# power_supply.net
KiCad netlist of a schematic drawn in Altium Designer
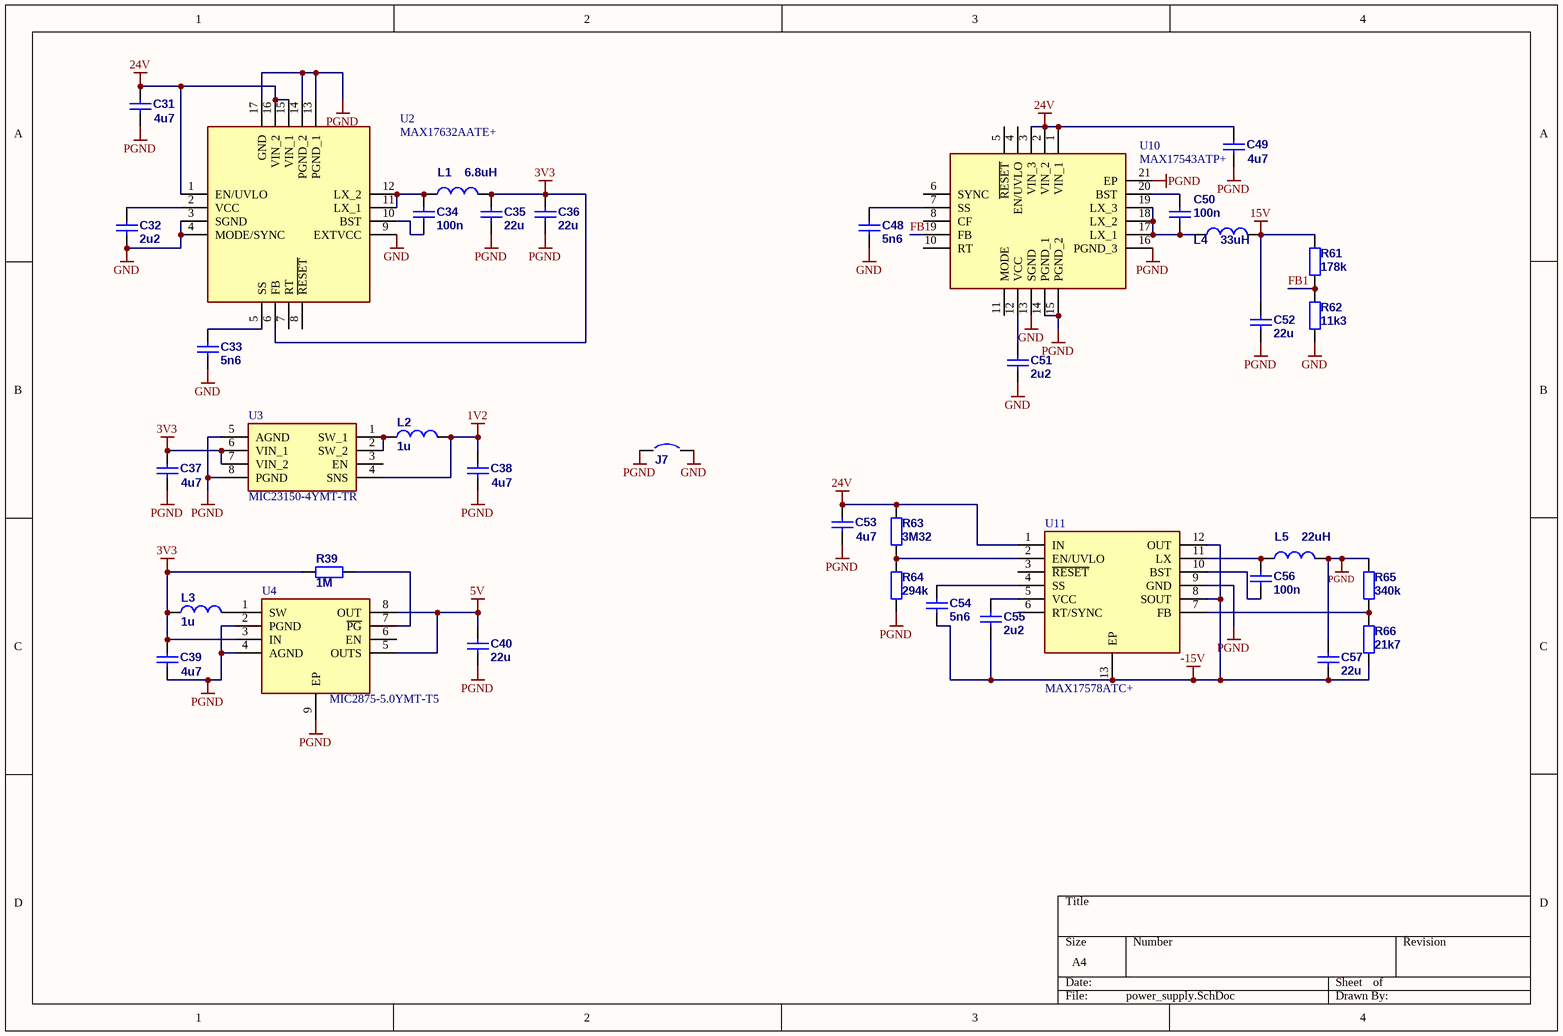
[diagram p0: power_supply.SchDoc]

(export (version "E")
  (design (tool "Eeschema 10.0.6"))
  (components
    (comp (ref "C31")
      (value "4u7")
      (footprint "C1206")
      (description "Capacitor")
      (libsource (lib "capacitors") (part "Cap"))
    )
    (comp (ref "C32")
      (value "2u2")
      (footprint "C0603")
      (description "Capacitor")
      (libsource (lib "capacitors") (part "Cap"))
    )
    (comp (ref "C33")
      (value "5n6")
      (footprint "C0603")
      (description "Capacitor")
      (libsource (lib "capacitors") (part "Cap"))
    )
    (comp (ref "C34")
      (value "100n")
      (footprint "C0603")
      (description "Capacitor")
      (libsource (lib "capacitors") (part "Cap"))
    )
    (comp (ref "C35")
      (value "22u")
      (footprint "C1206")
      (description "Capacitor")
      (libsource (lib "capacitors") (part "Cap"))
    )
    (comp (ref "C36")
      (value "22u")
      (footprint "C1206")
      (description "Capacitor")
      (libsource (lib "capacitors") (part "Cap"))
    )
    (comp (ref "C37")
      (value "4u7")
      (footprint "C1206")
      (description "Capacitor")
      (libsource (lib "capacitors") (part "Cap"))
    )
    (comp (ref "C38")
      (value "4u7")
      (footprint "C1206")
      (description "Capacitor")
      (libsource (lib "capacitors") (part "Cap"))
    )
    (comp (ref "C39")
      (value "4u7")
      (footprint "C1206")
      (description "Capacitor")
      (libsource (lib "capacitors") (part "Cap"))
    )
    (comp (ref "C40")
      (value "22u")
      (footprint "C1206")
      (description "Capacitor")
      (libsource (lib "capacitors") (part "Cap"))
    )
    (comp (ref "C48")
      (value "5n6")
      (footprint "C0603")
      (description "Capacitor")
      (libsource (lib "capacitors") (part "Cap"))
    )
    (comp (ref "C49")
      (value "4u7")
      (footprint "C1206")
      (description "Capacitor")
      (libsource (lib "capacitors") (part "Cap"))
    )
    (comp (ref "C50")
      (value "100n")
      (footprint "C0603")
      (description "Capacitor")
      (libsource (lib "capacitors") (part "Cap"))
    )
    (comp (ref "C51")
      (value "2u2")
      (footprint "C0603")
      (description "Capacitor")
      (libsource (lib "capacitors") (part "Cap"))
    )
    (comp (ref "C52")
      (value "22u")
      (footprint "C1206")
      (description "Capacitor")
      (libsource (lib "capacitors") (part "Cap"))
    )
    (comp (ref "C53")
      (value "4u7")
      (footprint "C1206")
      (description "Capacitor")
      (libsource (lib "capacitors") (part "Cap"))
    )
    (comp (ref "C54")
      (value "5n6")
      (footprint "C0603")
      (description "Capacitor")
      (libsource (lib "capacitors") (part "Cap"))
    )
    (comp (ref "C55")
      (value "2u2")
      (footprint "C0603")
      (description "Capacitor")
      (libsource (lib "capacitors") (part "Cap"))
    )
    (comp (ref "C56")
      (value "100n")
      (footprint "C0603")
      (description "Capacitor")
      (libsource (lib "capacitors") (part "Cap"))
    )
    (comp (ref "C57")
      (value "22u")
      (footprint "C1206")
      (description "Capacitor")
      (libsource (lib "capacitors") (part "Cap"))
    )
    (comp (ref "J7")
      (value "Circuit Breaker")
      (footprint "JMP2_0805_N_NC")
      (fields (field (name "PUBLISHER") "Altium Limited"))
      (libsource (lib "jumpers_and_circuit_brakers") (part "Circuit Breaker"))
    )
    (comp (ref "L1")
      (value "6.8uH")
      (footprint "DE1205")
      (description "DE1205-10")
      (libsource (lib "inductors") (part "DE1205-10"))
    )
    (comp (ref "L2")
      (value "1u")
      (footprint "L1210")
      (description "Inductor")
      (libsource (lib "inductors") (part "Ind"))
    )
    (comp (ref "L3")
      (value "1u")
      (footprint "L1210")
      (description "Inductor")
      (libsource (lib "inductors") (part "Ind"))
    )
    (comp (ref "L4")
      (value "33uH")
      (footprint "DE1205")
      (description "DE1205-22")
      (libsource (lib "inductors") (part "DE1205-22"))
    )
    (comp (ref "L5")
      (value "22uH")
      (footprint "DE1205")
      (description "DE1205-22")
      (libsource (lib "inductors") (part "DE1205-22"))
    )
    (comp (ref "R39")
      (value "1M")
      (footprint "R0603")
      (description "Resistor")
      (libsource (lib "") (part "Res_1"))
    )
    (comp (ref "R61")
      (value "178k")
      (footprint "R0603")
      (description "Resistor")
      (libsource (lib "resistors") (part "Res"))
    )
    (comp (ref "R62")
      (value "11k3")
      (footprint "R0603")
      (description "Resistor")
      (libsource (lib "resistors") (part "Res"))
    )
    (comp (ref "R63")
      (value "3M32")
      (footprint "R0603")
      (description "Resistor")
      (libsource (lib "resistors") (part "Res"))
    )
    (comp (ref "R64")
      (value "294k")
      (footprint "R0603")
      (description "Resistor")
      (libsource (lib "resistors") (part "Res"))
    )
    (comp (ref "R65")
      (value "340k")
      (footprint "R0603")
      (description "Resistor")
      (libsource (lib "resistors") (part "Res"))
    )
    (comp (ref "R66")
      (value "21k7")
      (footprint "R0603")
      (description "Resistor")
      (libsource (lib "resistors") (part "Res"))
    )
    (comp (ref "U2")
      (value "MAX17632AATE+")
      (footprint "SamacSys:QFN50P300X300X80-17N")
      (description "Integrated Circuit")
      (libsource (lib "*") (part "MAX17632AATE+"))
    )
    (comp (ref "U3")
      (value "MIC23150-4YMT-TR")
      (footprint "SamacSys:MIC231504YMTTR")
      (description "Integrated Circuit")
      (fields (field (name "MOUSER PART NUMBER") "998-MIC23150-4YMTTR"))
      (libsource (lib "*") (part "MIC23150-4YMT-TR"))
    )
    (comp (ref "U4")
      (value "MIC2875-5.0YMT-T5")
      (footprint "SamacSys:SON50P200X200X60-9N-D")
      (description "Integrated Circuit")
      (libsource (lib "*") (part "MIC2875-5.0YMT-T5"))
    )
    (comp (ref "U10")
      (value "MAX17543ATP+")
      (footprint "SamacSys:QFN50P400X400X80-21N")
      (description "Integrated Circuit")
      (libsource (lib "*") (part "MAX17543ATP+"))
    )
    (comp (ref "U11")
      (value "MAX17578ATC+")
      (footprint "SamacSys:SON50P300X300X80-13N")
      (description "Integrated Circuit")
      (libsource (lib "*") (part "MAX17578ATC+"))
    )
  )
  (nets
    (net (code "1") (name "-15V") (class "Default")
      (node (ref "C54") (pin "1") (pinfunction "1_1") (pintype "passive"))
      (node (ref "C55") (pin "1") (pinfunction "1_1") (pintype "passive"))
      (node (ref "C57") (pin "1") (pinfunction "1_1") (pintype "passive"))
      (node (ref "R66") (pin "1") (pinfunction "1_1") (pintype "passive"))
      (node (ref "U11") (pin "12") (pinfunction "OUT_12") (pintype "passive"))
      (node (ref "U11") (pin "13") (pinfunction "EP_13") (pintype "passive"))
      (node (ref "U11") (pin "8") (pinfunction "SOUT_8") (pintype "passive"))
    )
    (net (code "2") (name "/FB1") (class "Default")
      (node (ref "R61") (pin "1") (pinfunction "1_1") (pintype "passive"))
      (node (ref "R62") (pin "2") (pinfunction "2_2") (pintype "passive"))
      (node (ref "U10") (pin "9") (pinfunction "FB_9") (pintype "passive"))
    )
    (net (code "3") (name "1V2") (class "Default")
      (node (ref "C38") (pin "2") (pinfunction "2_2") (pintype "passive"))
      (node (ref "L2") (pin "2") (pinfunction "2_2") (pintype "passive"))
      (node (ref "U3") (pin "4") (pinfunction "SNS_4") (pintype "passive"))
    )
    (net (code "4") (name "3V3") (class "Default")
      (node (ref "C35") (pin "2") (pinfunction "2_2") (pintype "passive"))
      (node (ref "C36") (pin "2") (pinfunction "2_2") (pintype "passive"))
      (node (ref "C37") (pin "2") (pinfunction "2_2") (pintype "passive"))
      (node (ref "C39") (pin "2") (pinfunction "2_2") (pintype "passive"))
      (node (ref "L1") (pin "2") (pinfunction "2_2") (pintype "passive"))
      (node (ref "L3") (pin "1") (pinfunction "1_1") (pintype "passive"))
      (node (ref "R39") (pin "1") (pinfunction "1_1") (pintype "passive"))
      (node (ref "U2") (pin "6") (pinfunction "FB_6") (pintype "passive"))
      (node (ref "U3") (pin "6") (pinfunction "VIN_1_6") (pintype "passive"))
      (node (ref "U3") (pin "7") (pinfunction "VIN_2_7") (pintype "passive"))
      (node (ref "U4") (pin "3") (pinfunction "IN_3") (pintype "passive"))
    )
    (net (code "5") (name "5V") (class "Default")
      (node (ref "C40") (pin "2") (pinfunction "2_2") (pintype "passive"))
      (node (ref "U4") (pin "5") (pinfunction "OUTS_5") (pintype "passive"))
      (node (ref "U4") (pin "8") (pinfunction "OUT_8") (pintype "passive"))
    )
    (net (code "6") (name "15V") (class "Default")
      (node (ref "C52") (pin "2") (pinfunction "2_2") (pintype "passive"))
      (node (ref "L4") (pin "2") (pinfunction "2_2") (pintype "passive"))
      (node (ref "R61") (pin "2") (pinfunction "2_2") (pintype "passive"))
    )
    (net (code "7") (name "24V") (class "Default")
      (node (ref "C31") (pin "2") (pinfunction "2_2") (pintype "passive"))
      (node (ref "C49") (pin "2") (pinfunction "2_2") (pintype "passive"))
      (node (ref "C53") (pin "2") (pinfunction "2_2") (pintype "passive"))
      (node (ref "R63") (pin "2") (pinfunction "2_2") (pintype "passive"))
      (node (ref "U10") (pin "1") (pinfunction "VIN_1_1") (pintype "passive"))
      (node (ref "U10") (pin "2") (pinfunction "VIN_2_2") (pintype "passive"))
      (node (ref "U10") (pin "3") (pinfunction "VIN_3_3") (pintype "passive"))
      (node (ref "U11") (pin "1") (pinfunction "IN_1") (pintype "passive"))
      (node (ref "U2") (pin "1") (pinfunction "EN/UVLO_1") (pintype "passive"))
      (node (ref "U2") (pin "15") (pinfunction "VIN_1_15") (pintype "passive"))
      (node (ref "U2") (pin "16") (pinfunction "VIN_2_16") (pintype "passive"))
    )
    (net (code "8") (name "GND") (class "Default")
      (node (ref "C32") (pin "1") (pinfunction "1_1") (pintype "passive"))
      (node (ref "C33") (pin "1") (pinfunction "1_1") (pintype "passive"))
      (node (ref "C48") (pin "1") (pinfunction "1_1") (pintype "passive"))
      (node (ref "C51") (pin "1") (pinfunction "1_1") (pintype "passive"))
      (node (ref "J7") (pin "2") (pinfunction "2_2") (pintype "passive"))
      (node (ref "R62") (pin "1") (pinfunction "1_1") (pintype "passive"))
      (node (ref "U10") (pin "13") (pinfunction "SGND_13") (pintype "passive"))
      (node (ref "U2") (pin "3") (pinfunction "SGND_3") (pintype "passive"))
      (node (ref "U2") (pin "4") (pinfunction "MODE/SYNC_4") (pintype "passive"))
      (node (ref "U2") (pin "9") (pinfunction "EXTVCC_9") (pintype "passive"))
    )
    (net (code "9") (name "Net-(U2-BST)") (class "Default")
      (node (ref "C34") (pin "2") (pinfunction "2_2") (pintype "passive"))
      (node (ref "U2") (pin "10") (pinfunction "BST_10") (pintype "passive"))
    )
    (net (code "10") (name "Net-(U2-LX_1)") (class "Default")
      (node (ref "C34") (pin "1") (pinfunction "1_1") (pintype "passive"))
      (node (ref "L1") (pin "1") (pinfunction "1_1") (pintype "passive"))
      (node (ref "U2") (pin "11") (pinfunction "LX_1_11") (pintype "passive"))
      (node (ref "U2") (pin "12") (pinfunction "LX_2_12") (pintype "passive"))
    )
    (net (code "11") (name "Net-(U2-SS)") (class "Default")
      (node (ref "C33") (pin "2") (pinfunction "2_2") (pintype "passive"))
      (node (ref "U2") (pin "5") (pinfunction "SS_5") (pintype "passive"))
    )
    (net (code "12") (name "Net-(U2-VCC)") (class "Default")
      (node (ref "C32") (pin "2") (pinfunction "2_2") (pintype "passive"))
      (node (ref "U2") (pin "2") (pinfunction "VCC_2") (pintype "passive"))
    )
    (net (code "13") (name "Net-(U3-SW_1)") (class "Default")
      (node (ref "L2") (pin "1") (pinfunction "1_1") (pintype "passive"))
      (node (ref "U3") (pin "1") (pinfunction "SW_1_1") (pintype "passive"))
      (node (ref "U3") (pin "2") (pinfunction "SW_2_2") (pintype "passive"))
    )
    (net (code "14") (name "Net-(U4-SW)") (class "Default")
      (node (ref "L3") (pin "2") (pinfunction "2_2") (pintype "passive"))
      (node (ref "U4") (pin "1") (pinfunction "SW_1") (pintype "passive"))
    )
    (net (code "15") (name "Net-(U4-~{PG})") (class "Default")
      (node (ref "R39") (pin "2") (pinfunction "2_2") (pintype "passive"))
      (node (ref "U4") (pin "7") (pinfunction "~{PG}_7") (pintype "passive"))
    )
    (net (code "16") (name "Net-(U10-BST)") (class "Default")
      (node (ref "C50") (pin "2") (pinfunction "2_2") (pintype "passive"))
      (node (ref "U10") (pin "20") (pinfunction "BST_20") (pintype "passive"))
    )
    (net (code "17") (name "Net-(U10-LX_1)") (class "Default")
      (node (ref "C50") (pin "1") (pinfunction "1_1") (pintype "passive"))
      (node (ref "L4") (pin "1") (pinfunction "1_1") (pintype "passive"))
      (node (ref "U10") (pin "17") (pinfunction "LX_1_17") (pintype "passive"))
      (node (ref "U10") (pin "18") (pinfunction "LX_2_18") (pintype "passive"))
      (node (ref "U10") (pin "19") (pinfunction "LX_3_19") (pintype "passive"))
    )
    (net (code "18") (name "Net-(U10-SS)") (class "Default")
      (node (ref "C48") (pin "2") (pinfunction "2_2") (pintype "passive"))
      (node (ref "U10") (pin "7") (pinfunction "SS_7") (pintype "passive"))
    )
    (net (code "19") (name "Net-(U10-VCC)") (class "Default")
      (node (ref "C51") (pin "2") (pinfunction "2_2") (pintype "passive"))
      (node (ref "U10") (pin "12") (pinfunction "VCC_12") (pintype "passive"))
    )
    (net (code "20") (name "Net-(U11-BST)") (class "Default")
      (node (ref "C56") (pin "2") (pinfunction "2_2") (pintype "passive"))
      (node (ref "U11") (pin "10") (pinfunction "BST_10") (pintype "passive"))
    )
    (net (code "21") (name "Net-(U11-EN{slash}UVLO)") (class "Default")
      (node (ref "R63") (pin "1") (pinfunction "1_1") (pintype "passive"))
      (node (ref "R64") (pin "2") (pinfunction "2_2") (pintype "passive"))
      (node (ref "U11") (pin "2") (pinfunction "EN/UVLO_2") (pintype "passive"))
    )
    (net (code "22") (name "Net-(U11-FB)") (class "Default")
      (node (ref "R65") (pin "1") (pinfunction "1_1") (pintype "passive"))
      (node (ref "R66") (pin "2") (pinfunction "2_2") (pintype "passive"))
      (node (ref "U11") (pin "7") (pinfunction "FB_7") (pintype "passive"))
    )
    (net (code "23") (name "Net-(U11-LX)") (class "Default")
      (node (ref "C56") (pin "1") (pinfunction "1_1") (pintype "passive"))
      (node (ref "L5") (pin "1") (pinfunction "1_1") (pintype "passive"))
      (node (ref "U11") (pin "11") (pinfunction "LX_11") (pintype "passive"))
    )
    (net (code "24") (name "Net-(U11-SS)") (class "Default")
      (node (ref "C54") (pin "2") (pinfunction "2_2") (pintype "passive"))
      (node (ref "U11") (pin "4") (pinfunction "SS_4") (pintype "passive"))
    )
    (net (code "25") (name "Net-(U11-VCC)") (class "Default")
      (node (ref "C55") (pin "2") (pinfunction "2_2") (pintype "passive"))
      (node (ref "U11") (pin "5") (pinfunction "VCC_5") (pintype "passive"))
    )
    (net (code "26") (name "PGND") (class "Default")
      (node (ref "C31") (pin "1") (pinfunction "1_1") (pintype "passive"))
      (node (ref "C35") (pin "1") (pinfunction "1_1") (pintype "passive"))
      (node (ref "C36") (pin "1") (pinfunction "1_1") (pintype "passive"))
      (node (ref "C37") (pin "1") (pinfunction "1_1") (pintype "passive"))
      (node (ref "C38") (pin "1") (pinfunction "1_1") (pintype "passive"))
      (node (ref "C39") (pin "1") (pinfunction "1_1") (pintype "passive"))
      (node (ref "C40") (pin "1") (pinfunction "1_1") (pintype "passive"))
      (node (ref "C49") (pin "1") (pinfunction "1_1") (pintype "passive"))
      (node (ref "C52") (pin "1") (pinfunction "1_1") (pintype "passive"))
      (node (ref "C53") (pin "1") (pinfunction "1_1") (pintype "passive"))
      (node (ref "C57") (pin "2") (pinfunction "2_2") (pintype "passive"))
      (node (ref "J7") (pin "1") (pinfunction "1_1") (pintype "passive"))
      (node (ref "L5") (pin "2") (pinfunction "2_2") (pintype "passive"))
      (node (ref "R64") (pin "1") (pinfunction "1_1") (pintype "passive"))
      (node (ref "R65") (pin "2") (pinfunction "2_2") (pintype "passive"))
      (node (ref "U10") (pin "14") (pinfunction "PGND_1_14") (pintype "passive"))
      (node (ref "U10") (pin "15") (pinfunction "PGND_2_15") (pintype "passive"))
      (node (ref "U10") (pin "16") (pinfunction "PGND_3_16") (pintype "passive"))
      (node (ref "U10") (pin "21") (pinfunction "EP_21") (pintype "passive"))
      (node (ref "U11") (pin "9") (pinfunction "GND_9") (pintype "passive"))
      (node (ref "U2") (pin "13") (pinfunction "PGND_1_13") (pintype "passive"))
      (node (ref "U2") (pin "14") (pinfunction "PGND_2_14") (pintype "passive"))
      (node (ref "U2") (pin "17") (pinfunction "GND_17") (pintype "passive"))
      (node (ref "U3") (pin "5") (pinfunction "AGND_5") (pintype "passive"))
      (node (ref "U3") (pin "8") (pinfunction "PGND_8") (pintype "passive"))
      (node (ref "U4") (pin "2") (pinfunction "PGND_2") (pintype "passive"))
      (node (ref "U4") (pin "4") (pinfunction "AGND_4") (pintype "passive"))
      (node (ref "U4") (pin "9") (pinfunction "EP_9") (pintype "passive"))
    )
    (net (code "27") (name "unconnected-(U2-RT-Pad7)") (class "Default")
      (node (ref "U2") (pin "7") (pinfunction "RT_7") (pintype "passive"))
    )
    (net (code "28") (name "unconnected-(U2-~{RESET}-Pad8)") (class "Default")
      (node (ref "U2") (pin "8") (pinfunction "~{RESET}_8") (pintype "passive"))
    )
    (net (code "29") (name "unconnected-(U3-EN-Pad3)") (class "Default")
      (node (ref "U3") (pin "3") (pinfunction "EN_3") (pintype "passive"))
    )
    (net (code "30") (name "unconnected-(U4-EN-Pad6)") (class "Default")
      (node (ref "U4") (pin "6") (pinfunction "EN_6") (pintype "passive"))
    )
    (net (code "31") (name "unconnected-(U10-CF-Pad8)") (class "Default")
      (node (ref "U10") (pin "8") (pinfunction "CF_8") (pintype "passive"))
    )
    (net (code "32") (name "unconnected-(U10-EN{slash}UVLO-Pad4)") (class "Default")
      (node (ref "U10") (pin "4") (pinfunction "EN/UVLO_4") (pintype "passive"))
    )
    (net (code "33") (name "unconnected-(U10-MODE-Pad11)") (class "Default")
      (node (ref "U10") (pin "11") (pinfunction "MODE_11") (pintype "passive"))
    )
    (net (code "34") (name "unconnected-(U10-RT-Pad10)") (class "Default")
      (node (ref "U10") (pin "10") (pinfunction "RT_10") (pintype "passive"))
    )
    (net (code "35") (name "unconnected-(U10-SYNC-Pad6)") (class "Default")
      (node (ref "U10") (pin "6") (pinfunction "SYNC_6") (pintype "passive"))
    )
    (net (code "36") (name "unconnected-(U10-~{RESET}-Pad5)") (class "Default")
      (node (ref "U10") (pin "5") (pinfunction "~{RESET}_5") (pintype "passive"))
    )
    (net (code "37") (name "unconnected-(U11-RT{slash}SYNC-Pad6)") (class "Default")
      (node (ref "U11") (pin "6") (pinfunction "RT/SYNC_6") (pintype "passive"))
    )
    (net (code "38") (name "unconnected-(U11-~{RESET}-Pad3)") (class "Default")
      (node (ref "U11") (pin "3") (pinfunction "~{RESET}_3") (pintype "passive"))
    )
  )
)
